# xmosio1.net
KiCad netlist of a schematic drawn in EAGLE
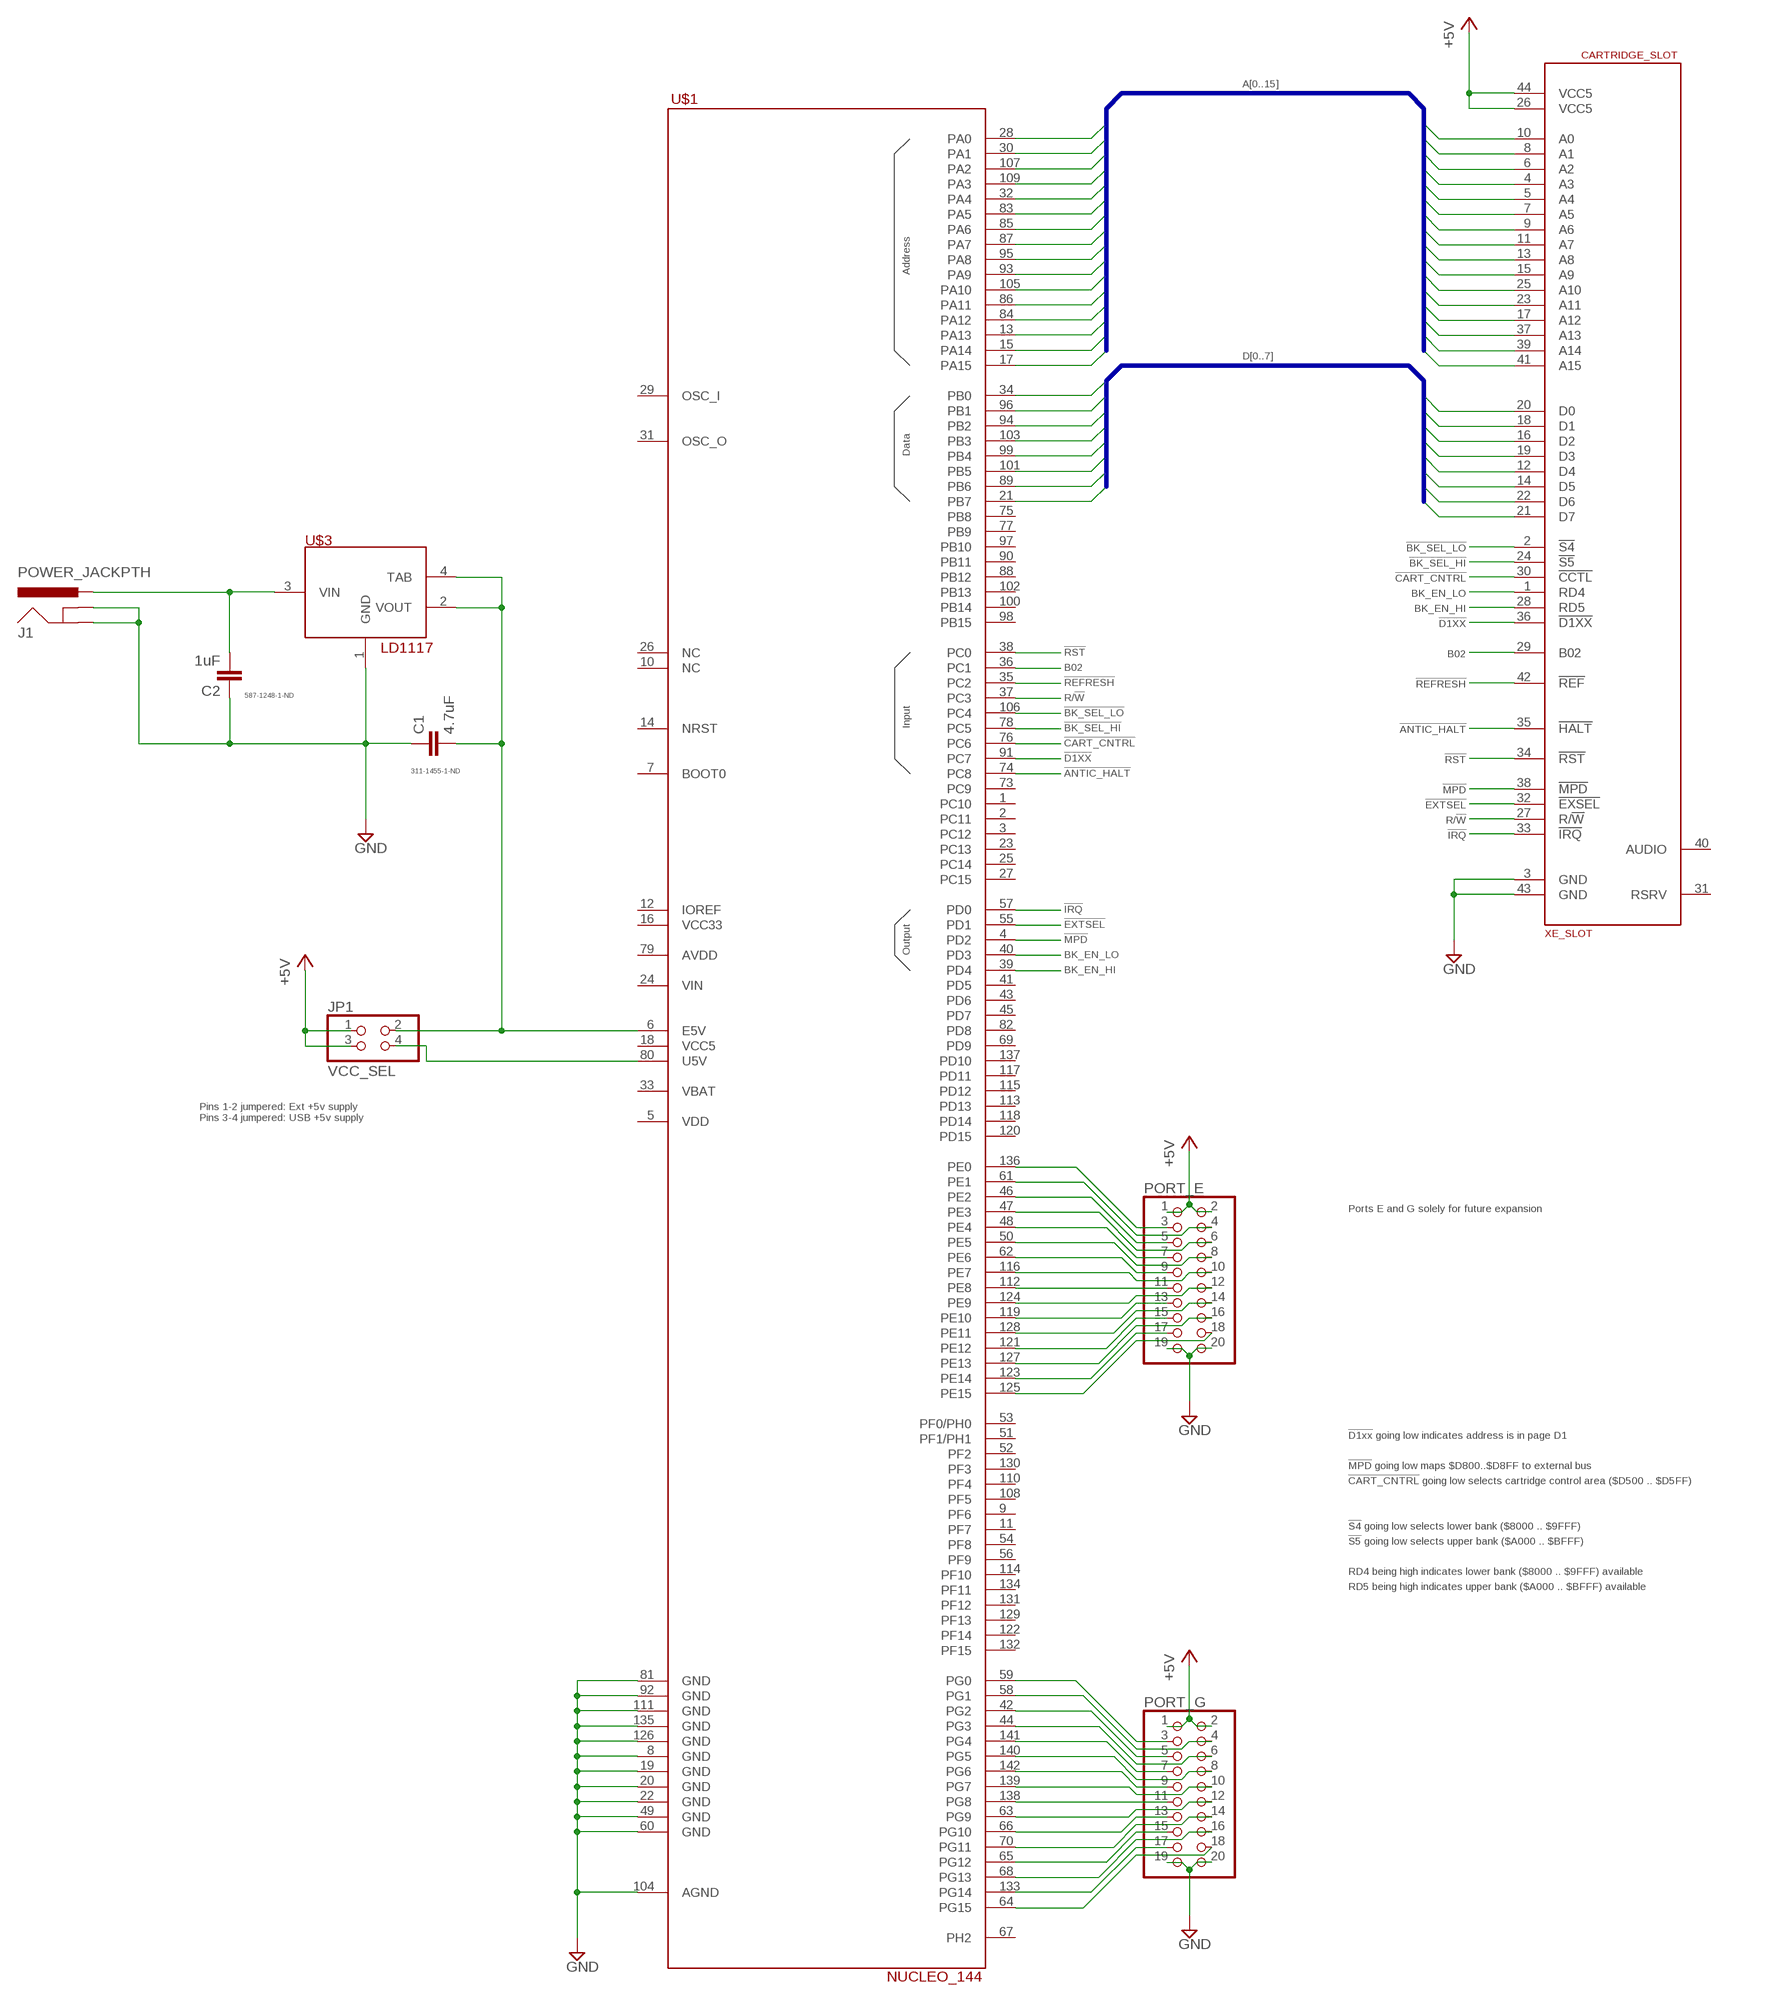
[diagram p0: schematic, sheet 1]

(export (version "E")
  (design (tool "Eeschema 10.0.6"))
  (components
    (comp (ref "C1")
      (value "4.7uF")
      (footprint "eagle-import:C0603")
      (libsource (lib "eagle-import") (part "C-EUC0603"))
    )
    (comp (ref "C2")
      (value "1uF")
      (footprint "eagle-import:C0603")
      (libsource (lib "eagle-import") (part "C-EUC0603"))
    )
    (comp (ref "CARTRIDGE_SLOT")
      (value "XE_SLOT")
      (footprint "eagle-import:XE_SLOT")
      (libsource (lib "eagle-import") (part "XE_SLOT"))
    )
    (comp (ref "J1")
      (value "POWER_JACKPTH")
      (footprint "eagle-import:POWER_JACK_PTH")
      (libsource (lib "eagle-import") (part "POWER_JACKPTH"))
    )
    (comp (ref "JP1")
      (value "VCC_SEL")
      (footprint "eagle-import:2X02")
      (libsource (lib "eagle-import") (part "PINHD-2X2"))
    )
    (comp (ref "PORT_E")
      (value "PINHD-2X10")
      (footprint "eagle-import:2X10")
      (libsource (lib "eagle-import") (part "PINHD-2X10"))
    )
    (comp (ref "PORT_G")
      (value "PINHD-2X10")
      (footprint "eagle-import:2X10")
      (libsource (lib "eagle-import") (part "PINHD-2X10"))
    )
    (comp (ref "U$1")
      (value "NUCLEO_144")
      (footprint "eagle-import:NUCLEO_144")
      (libsource (lib "eagle-import") (part "NUCLEO_144"))
    )
    (comp (ref "U$3")
      (value "LD1117")
      (footprint "eagle-import:SOT223")
      (libsource (lib "eagle-import") (part "LD1117"))
    )
  )
  (nets
    (net (code "1") (name "+5V") (class "Default")
      (node (ref "CARTRIDGE_SLOT") (pin "26") (pinfunction "VCC5_26") (pintype "bidirectional"))
      (node (ref "CARTRIDGE_SLOT") (pin "44") (pinfunction "VCC5_44") (pintype "bidirectional"))
      (node (ref "JP1") (pin "1") (pinfunction "1_1") (pintype "passive"))
      (node (ref "JP1") (pin "3") (pinfunction "3_3") (pintype "passive"))
      (node (ref "PORT_E") (pin "1") (pinfunction "1_1") (pintype "passive"))
      (node (ref "PORT_E") (pin "2") (pinfunction "2_2") (pintype "passive"))
      (node (ref "PORT_G") (pin "1") (pinfunction "1_1") (pintype "passive"))
      (node (ref "PORT_G") (pin "2") (pinfunction "2_2") (pintype "passive"))
    )
    (net (code "2") (name "/A0") (class "Default")
      (node (ref "CARTRIDGE_SLOT") (pin "10") (pinfunction "A0_10") (pintype "bidirectional"))
      (node (ref "U$1") (pin "28") (pinfunction "PA0_28") (pintype "bidirectional"))
    )
    (net (code "3") (name "/A1") (class "Default")
      (node (ref "CARTRIDGE_SLOT") (pin "8") (pinfunction "A1_8") (pintype "bidirectional"))
      (node (ref "U$1") (pin "30") (pinfunction "PA1_30") (pintype "bidirectional"))
    )
    (net (code "4") (name "/A2") (class "Default")
      (node (ref "CARTRIDGE_SLOT") (pin "6") (pinfunction "A2_6") (pintype "bidirectional"))
      (node (ref "U$1") (pin "107") (pinfunction "PA2_107") (pintype "bidirectional"))
    )
    (net (code "5") (name "/A3") (class "Default")
      (node (ref "CARTRIDGE_SLOT") (pin "4") (pinfunction "A3_4") (pintype "bidirectional"))
      (node (ref "U$1") (pin "109") (pinfunction "PA3_109") (pintype "bidirectional"))
    )
    (net (code "6") (name "/A4") (class "Default")
      (node (ref "CARTRIDGE_SLOT") (pin "5") (pinfunction "A4_5") (pintype "bidirectional"))
      (node (ref "U$1") (pin "32") (pinfunction "PA4_32") (pintype "bidirectional"))
    )
    (net (code "7") (name "/A5") (class "Default")
      (node (ref "CARTRIDGE_SLOT") (pin "7") (pinfunction "A5_7") (pintype "bidirectional"))
      (node (ref "U$1") (pin "83") (pinfunction "PA5_83") (pintype "bidirectional"))
    )
    (net (code "8") (name "/A6") (class "Default")
      (node (ref "CARTRIDGE_SLOT") (pin "9") (pinfunction "A6_9") (pintype "bidirectional"))
      (node (ref "U$1") (pin "85") (pinfunction "PA6_85") (pintype "bidirectional"))
    )
    (net (code "9") (name "/A7") (class "Default")
      (node (ref "CARTRIDGE_SLOT") (pin "11") (pinfunction "A7_11") (pintype "bidirectional"))
      (node (ref "U$1") (pin "87") (pinfunction "PA7_87") (pintype "bidirectional"))
    )
    (net (code "10") (name "/A8") (class "Default")
      (node (ref "CARTRIDGE_SLOT") (pin "13") (pinfunction "A8_13") (pintype "bidirectional"))
      (node (ref "U$1") (pin "95") (pinfunction "PA8_95") (pintype "bidirectional"))
    )
    (net (code "11") (name "/A9") (class "Default")
      (node (ref "CARTRIDGE_SLOT") (pin "15") (pinfunction "A9_15") (pintype "bidirectional"))
      (node (ref "U$1") (pin "93") (pinfunction "PA9_93") (pintype "bidirectional"))
    )
    (net (code "12") (name "/A10") (class "Default")
      (node (ref "CARTRIDGE_SLOT") (pin "25") (pinfunction "A10_25") (pintype "bidirectional"))
      (node (ref "U$1") (pin "105") (pinfunction "PA10_105") (pintype "bidirectional"))
    )
    (net (code "13") (name "/A11") (class "Default")
      (node (ref "CARTRIDGE_SLOT") (pin "23") (pinfunction "A11_23") (pintype "bidirectional"))
      (node (ref "U$1") (pin "86") (pinfunction "PA11_86") (pintype "bidirectional"))
    )
    (net (code "14") (name "/A12") (class "Default")
      (node (ref "CARTRIDGE_SLOT") (pin "17") (pinfunction "A12_17") (pintype "bidirectional"))
      (node (ref "U$1") (pin "84") (pinfunction "PA12_84") (pintype "bidirectional"))
    )
    (net (code "15") (name "/A13") (class "Default")
      (node (ref "CARTRIDGE_SLOT") (pin "37") (pinfunction "A13_37") (pintype "bidirectional"))
      (node (ref "U$1") (pin "13") (pinfunction "PA13_13") (pintype "bidirectional"))
    )
    (net (code "16") (name "/A14") (class "Default")
      (node (ref "CARTRIDGE_SLOT") (pin "39") (pinfunction "A14_39") (pintype "bidirectional"))
      (node (ref "U$1") (pin "15") (pinfunction "PA14_15") (pintype "bidirectional"))
    )
    (net (code "17") (name "/A15") (class "Default")
      (node (ref "CARTRIDGE_SLOT") (pin "41") (pinfunction "A15_41") (pintype "bidirectional"))
      (node (ref "U$1") (pin "17") (pinfunction "PA15_17") (pintype "bidirectional"))
    )
    (net (code "19") (name "/B02") (class "Default")
      (node (ref "CARTRIDGE_SLOT") (pin "29") (pinfunction "B02_29") (pintype "bidirectional"))
      (node (ref "U$1") (pin "36") (pinfunction "PC1_36") (pintype "bidirectional"))
    )
    (net (code "20") (name "/BK_EN_HI") (class "Default")
      (node (ref "CARTRIDGE_SLOT") (pin "28") (pinfunction "RD5_28") (pintype "bidirectional"))
      (node (ref "U$1") (pin "39") (pinfunction "PD4_39") (pintype "bidirectional"))
    )
    (net (code "21") (name "/BK_EN_LO") (class "Default")
      (node (ref "CARTRIDGE_SLOT") (pin "1") (pinfunction "RD4_1") (pintype "bidirectional"))
      (node (ref "U$1") (pin "40") (pinfunction "PD3_40") (pintype "bidirectional"))
    )
    (net (code "22") (name "/D0") (class "Default")
      (node (ref "CARTRIDGE_SLOT") (pin "20") (pinfunction "D0_20") (pintype "bidirectional"))
      (node (ref "U$1") (pin "34") (pinfunction "PB0_34") (pintype "bidirectional"))
    )
    (net (code "23") (name "/D1") (class "Default")
      (node (ref "CARTRIDGE_SLOT") (pin "18") (pinfunction "D1_18") (pintype "bidirectional"))
      (node (ref "U$1") (pin "96") (pinfunction "PB1_96") (pintype "bidirectional"))
    )
    (net (code "24") (name "/D2") (class "Default")
      (node (ref "CARTRIDGE_SLOT") (pin "16") (pinfunction "D2_16") (pintype "bidirectional"))
      (node (ref "U$1") (pin "94") (pinfunction "PB2_94") (pintype "bidirectional"))
    )
    (net (code "25") (name "/D3") (class "Default")
      (node (ref "CARTRIDGE_SLOT") (pin "19") (pinfunction "D3_19") (pintype "bidirectional"))
      (node (ref "U$1") (pin "103") (pinfunction "PB3_103") (pintype "bidirectional"))
    )
    (net (code "26") (name "/D4") (class "Default")
      (node (ref "CARTRIDGE_SLOT") (pin "12") (pinfunction "D4_12") (pintype "bidirectional"))
      (node (ref "U$1") (pin "99") (pinfunction "PB4_99") (pintype "bidirectional"))
    )
    (net (code "27") (name "/D5") (class "Default")
      (node (ref "CARTRIDGE_SLOT") (pin "14") (pinfunction "D5_14") (pintype "bidirectional"))
      (node (ref "U$1") (pin "101") (pinfunction "PB5_101") (pintype "bidirectional"))
    )
    (net (code "28") (name "/D6") (class "Default")
      (node (ref "CARTRIDGE_SLOT") (pin "22") (pinfunction "D6_22") (pintype "bidirectional"))
      (node (ref "U$1") (pin "89") (pinfunction "PB6_89") (pintype "bidirectional"))
    )
    (net (code "29") (name "/D7") (class "Default")
      (node (ref "CARTRIDGE_SLOT") (pin "21") (pinfunction "D7_21") (pintype "bidirectional"))
      (node (ref "U$1") (pin "21") (pinfunction "PB7_21") (pintype "bidirectional"))
    )
    (net (code "31") (name "/R{slash}~{W}") (class "Default")
      (node (ref "CARTRIDGE_SLOT") (pin "27") (pinfunction "R/~{W}_27") (pintype "bidirectional"))
      (node (ref "U$1") (pin "37") (pinfunction "PC3_37") (pintype "bidirectional"))
    )
    (net (code "32") (name "/~{ANTIC_HALT}") (class "Default")
      (node (ref "CARTRIDGE_SLOT") (pin "35") (pinfunction "~{HALT}_35") (pintype "bidirectional"))
      (node (ref "U$1") (pin "74") (pinfunction "PC8_74") (pintype "bidirectional"))
    )
    (net (code "33") (name "/~{BK_SEL_HI}") (class "Default")
      (node (ref "CARTRIDGE_SLOT") (pin "24") (pinfunction "~{S5}_24") (pintype "bidirectional"))
      (node (ref "U$1") (pin "78") (pinfunction "PC5_78") (pintype "bidirectional"))
    )
    (net (code "34") (name "/~{BK_SEL_LO}") (class "Default")
      (node (ref "CARTRIDGE_SLOT") (pin "2") (pinfunction "~{S4}_2") (pintype "bidirectional"))
      (node (ref "U$1") (pin "106") (pinfunction "PC4_106") (pintype "bidirectional"))
    )
    (net (code "35") (name "/~{CART_CNTRL}") (class "Default")
      (node (ref "CARTRIDGE_SLOT") (pin "30") (pinfunction "~{CCTL}_30") (pintype "bidirectional"))
      (node (ref "U$1") (pin "76") (pinfunction "PC6_76") (pintype "bidirectional"))
    )
    (net (code "36") (name "/~{D1XX}") (class "Default")
      (node (ref "CARTRIDGE_SLOT") (pin "36") (pinfunction "~{D1XX}_36") (pintype "bidirectional"))
      (node (ref "U$1") (pin "91") (pinfunction "PC7_91") (pintype "bidirectional"))
    )
    (net (code "37") (name "/~{EXTSEL}") (class "Default")
      (node (ref "CARTRIDGE_SLOT") (pin "32") (pinfunction "~{EXSEL}_32") (pintype "bidirectional"))
      (node (ref "U$1") (pin "55") (pinfunction "PD1_55") (pintype "bidirectional"))
    )
    (net (code "38") (name "/~{IRQ}") (class "Default")
      (node (ref "CARTRIDGE_SLOT") (pin "33") (pinfunction "~{IRQ}_33") (pintype "bidirectional"))
      (node (ref "U$1") (pin "57") (pinfunction "PD0_57") (pintype "bidirectional"))
    )
    (net (code "39") (name "/~{MPD}") (class "Default")
      (node (ref "CARTRIDGE_SLOT") (pin "38") (pinfunction "~{MPD}_38") (pintype "bidirectional"))
      (node (ref "U$1") (pin "4") (pinfunction "PD2_4") (pintype "bidirectional"))
    )
    (net (code "40") (name "/~{REFRESH}") (class "Default")
      (node (ref "CARTRIDGE_SLOT") (pin "42") (pinfunction "~{REF}_42") (pintype "bidirectional"))
      (node (ref "U$1") (pin "35") (pinfunction "PC2_35") (pintype "bidirectional"))
    )
    (net (code "41") (name "/~{RST}") (class "Default")
      (node (ref "CARTRIDGE_SLOT") (pin "34") (pinfunction "~{RST}_34") (pintype "bidirectional"))
      (node (ref "U$1") (pin "38") (pinfunction "PC0_38") (pintype "bidirectional"))
    )
    (net (code "42") (name "GND") (class "Default")
      (node (ref "C1") (pin "1") (pinfunction "1_1") (pintype "passive"))
      (node (ref "C2") (pin "1") (pinfunction "1_1") (pintype "passive"))
      (node (ref "CARTRIDGE_SLOT") (pin "3") (pinfunction "GND_3") (pintype "bidirectional"))
      (node (ref "CARTRIDGE_SLOT") (pin "43") (pinfunction "GND_43") (pintype "bidirectional"))
      (node (ref "J1") (pin "GND") (pinfunction "GND_GND") (pintype "bidirectional"))
      (node (ref "J1") (pin "GNDBREAK") (pinfunction "GNDBREAK_GNDBREAK") (pintype "bidirectional"))
      (node (ref "PORT_E") (pin "19") (pinfunction "19_19") (pintype "passive"))
      (node (ref "PORT_E") (pin "20") (pinfunction "20_20") (pintype "passive"))
      (node (ref "PORT_G") (pin "19") (pinfunction "19_19") (pintype "passive"))
      (node (ref "PORT_G") (pin "20") (pinfunction "20_20") (pintype "passive"))
      (node (ref "U$1") (pin "104") (pinfunction "AGND_104") (pintype "bidirectional"))
      (node (ref "U$1") (pin "111") (pinfunction "GND_111") (pintype "bidirectional"))
      (node (ref "U$1") (pin "126") (pinfunction "GND_126") (pintype "bidirectional"))
      (node (ref "U$1") (pin "135") (pinfunction "GND_135") (pintype "bidirectional"))
      (node (ref "U$1") (pin "19") (pinfunction "GND_19") (pintype "bidirectional"))
      (node (ref "U$1") (pin "20") (pinfunction "GND_20") (pintype "bidirectional"))
      (node (ref "U$1") (pin "22") (pinfunction "GND_22") (pintype "bidirectional"))
      (node (ref "U$1") (pin "49") (pinfunction "GND_49") (pintype "bidirectional"))
      (node (ref "U$1") (pin "60") (pinfunction "GND_60") (pintype "bidirectional"))
      (node (ref "U$1") (pin "8") (pinfunction "GND_8") (pintype "bidirectional"))
      (node (ref "U$1") (pin "81") (pinfunction "GND_81") (pintype "bidirectional"))
      (node (ref "U$1") (pin "92") (pinfunction "GND_92") (pintype "bidirectional"))
      (node (ref "U$3") (pin "1") (pinfunction "GND_1") (pintype "bidirectional"))
    )
    (net (code "43") (name "Net-(U$1-E5V)") (class "Default")
      (node (ref "C1") (pin "2") (pinfunction "2_2") (pintype "passive"))
      (node (ref "JP1") (pin "2") (pinfunction "2_2") (pintype "passive"))
      (node (ref "U$1") (pin "6") (pinfunction "E5V_6") (pintype "bidirectional"))
      (node (ref "U$3") (pin "2") (pinfunction "VOUT_2") (pintype "bidirectional"))
      (node (ref "U$3") (pin "4") (pinfunction "TAB_4") (pintype "bidirectional"))
    )
    (net (code "44") (name "Net-(U$1-PE0)") (class "Default")
      (node (ref "PORT_E") (pin "3") (pinfunction "3_3") (pintype "passive"))
      (node (ref "U$1") (pin "136") (pinfunction "PE0_136") (pintype "bidirectional"))
    )
    (net (code "45") (name "Net-(U$1-PE1)") (class "Default")
      (node (ref "PORT_E") (pin "4") (pinfunction "4_4") (pintype "passive"))
      (node (ref "U$1") (pin "61") (pinfunction "PE1_61") (pintype "bidirectional"))
    )
    (net (code "46") (name "Net-(U$1-PE2)") (class "Default")
      (node (ref "PORT_E") (pin "5") (pinfunction "5_5") (pintype "passive"))
      (node (ref "U$1") (pin "46") (pinfunction "PE2_46") (pintype "bidirectional"))
    )
    (net (code "47") (name "Net-(U$1-PE3)") (class "Default")
      (node (ref "PORT_E") (pin "6") (pinfunction "6_6") (pintype "passive"))
      (node (ref "U$1") (pin "47") (pinfunction "PE3_47") (pintype "bidirectional"))
    )
    (net (code "48") (name "Net-(U$1-PE4)") (class "Default")
      (node (ref "PORT_E") (pin "7") (pinfunction "7_7") (pintype "passive"))
      (node (ref "U$1") (pin "48") (pinfunction "PE4_48") (pintype "bidirectional"))
    )
    (net (code "49") (name "Net-(U$1-PE5)") (class "Default")
      (node (ref "PORT_E") (pin "8") (pinfunction "8_8") (pintype "passive"))
      (node (ref "U$1") (pin "50") (pinfunction "PE5_50") (pintype "bidirectional"))
    )
    (net (code "50") (name "Net-(U$1-PE6)") (class "Default")
      (node (ref "PORT_E") (pin "9") (pinfunction "9_9") (pintype "passive"))
      (node (ref "U$1") (pin "62") (pinfunction "PE6_62") (pintype "bidirectional"))
    )
    (net (code "51") (name "Net-(U$1-PE7)") (class "Default")
      (node (ref "PORT_E") (pin "10") (pinfunction "10_10") (pintype "passive"))
      (node (ref "U$1") (pin "116") (pinfunction "PE7_116") (pintype "bidirectional"))
    )
    (net (code "52") (name "Net-(U$1-PE8)") (class "Default")
      (node (ref "PORT_E") (pin "11") (pinfunction "11_11") (pintype "passive"))
      (node (ref "U$1") (pin "112") (pinfunction "PE8_112") (pintype "bidirectional"))
    )
    (net (code "53") (name "Net-(U$1-PE9)") (class "Default")
      (node (ref "PORT_E") (pin "12") (pinfunction "12_12") (pintype "passive"))
      (node (ref "U$1") (pin "124") (pinfunction "PE9_124") (pintype "bidirectional"))
    )
    (net (code "54") (name "Net-(U$1-PE10)") (class "Default")
      (node (ref "PORT_E") (pin "13") (pinfunction "13_13") (pintype "passive"))
      (node (ref "U$1") (pin "119") (pinfunction "PE10_119") (pintype "bidirectional"))
    )
    (net (code "55") (name "Net-(U$1-PE11)") (class "Default")
      (node (ref "PORT_E") (pin "14") (pinfunction "14_14") (pintype "passive"))
      (node (ref "U$1") (pin "128") (pinfunction "PE11_128") (pintype "bidirectional"))
    )
    (net (code "56") (name "Net-(U$1-PE12)") (class "Default")
      (node (ref "PORT_E") (pin "15") (pinfunction "15_15") (pintype "passive"))
      (node (ref "U$1") (pin "121") (pinfunction "PE12_121") (pintype "bidirectional"))
    )
    (net (code "57") (name "Net-(U$1-PE13)") (class "Default")
      (node (ref "PORT_E") (pin "16") (pinfunction "16_16") (pintype "passive"))
      (node (ref "U$1") (pin "127") (pinfunction "PE13_127") (pintype "bidirectional"))
    )
    (net (code "58") (name "Net-(U$1-PE14)") (class "Default")
      (node (ref "PORT_E") (pin "17") (pinfunction "17_17") (pintype "passive"))
      (node (ref "U$1") (pin "123") (pinfunction "PE14_123") (pintype "bidirectional"))
    )
    (net (code "59") (name "Net-(U$1-PE15)") (class "Default")
      (node (ref "PORT_E") (pin "18") (pinfunction "18_18") (pintype "passive"))
      (node (ref "U$1") (pin "125") (pinfunction "PE15_125") (pintype "bidirectional"))
    )
    (net (code "60") (name "Net-(U$1-PG0)") (class "Default")
      (node (ref "PORT_G") (pin "3") (pinfunction "3_3") (pintype "passive"))
      (node (ref "U$1") (pin "59") (pinfunction "PG0_59") (pintype "bidirectional"))
    )
    (net (code "61") (name "Net-(U$1-PG1)") (class "Default")
      (node (ref "PORT_G") (pin "4") (pinfunction "4_4") (pintype "passive"))
      (node (ref "U$1") (pin "58") (pinfunction "PG1_58") (pintype "bidirectional"))
    )
    (net (code "62") (name "Net-(U$1-PG2)") (class "Default")
      (node (ref "PORT_G") (pin "5") (pinfunction "5_5") (pintype "passive"))
      (node (ref "U$1") (pin "42") (pinfunction "PG2_42") (pintype "bidirectional"))
    )
    (net (code "63") (name "Net-(U$1-PG3)") (class "Default")
      (node (ref "PORT_G") (pin "6") (pinfunction "6_6") (pintype "passive"))
      (node (ref "U$1") (pin "44") (pinfunction "PG3_44") (pintype "bidirectional"))
    )
    (net (code "64") (name "Net-(U$1-PG4)") (class "Default")
      (node (ref "PORT_G") (pin "7") (pinfunction "7_7") (pintype "passive"))
      (node (ref "U$1") (pin "141") (pinfunction "PG4_141") (pintype "bidirectional"))
    )
    (net (code "65") (name "Net-(U$1-PG5)") (class "Default")
      (node (ref "PORT_G") (pin "8") (pinfunction "8_8") (pintype "passive"))
      (node (ref "U$1") (pin "140") (pinfunction "PG5_140") (pintype "bidirectional"))
    )
    (net (code "66") (name "Net-(U$1-PG6)") (class "Default")
      (node (ref "PORT_G") (pin "9") (pinfunction "9_9") (pintype "passive"))
      (node (ref "U$1") (pin "142") (pinfunction "PG6_142") (pintype "bidirectional"))
    )
    (net (code "67") (name "Net-(U$1-PG7)") (class "Default")
      (node (ref "PORT_G") (pin "10") (pinfunction "10_10") (pintype "passive"))
      (node (ref "U$1") (pin "139") (pinfunction "PG7_139") (pintype "bidirectional"))
    )
    (net (code "68") (name "Net-(U$1-PG8)") (class "Default")
      (node (ref "PORT_G") (pin "11") (pinfunction "11_11") (pintype "passive"))
      (node (ref "U$1") (pin "138") (pinfunction "PG8_138") (pintype "bidirectional"))
    )
    (net (code "69") (name "Net-(U$1-PG9)") (class "Default")
      (node (ref "PORT_G") (pin "12") (pinfunction "12_12") (pintype "passive"))
      (node (ref "U$1") (pin "63") (pinfunction "PG9_63") (pintype "bidirectional"))
    )
    (net (code "70") (name "Net-(U$1-PG10)") (class "Default")
      (node (ref "PORT_G") (pin "13") (pinfunction "13_13") (pintype "passive"))
      (node (ref "U$1") (pin "66") (pinfunction "PG10_66") (pintype "bidirectional"))
    )
    (net (code "71") (name "Net-(U$1-PG11)") (class "Default")
      (node (ref "PORT_G") (pin "14") (pinfunction "14_14") (pintype "passive"))
      (node (ref "U$1") (pin "70") (pinfunction "PG11_70") (pintype "bidirectional"))
    )
    (net (code "72") (name "Net-(U$1-PG12)") (class "Default")
      (node (ref "PORT_G") (pin "15") (pinfunction "15_15") (pintype "passive"))
      (node (ref "U$1") (pin "65") (pinfunction "PG12_65") (pintype "bidirectional"))
    )
    (net (code "73") (name "Net-(U$1-PG13)") (class "Default")
      (node (ref "PORT_G") (pin "16") (pinfunction "16_16") (pintype "passive"))
      (node (ref "U$1") (pin "68") (pinfunction "PG13_68") (pintype "bidirectional"))
    )
    (net (code "74") (name "Net-(U$1-PG14)") (class "Default")
      (node (ref "PORT_G") (pin "17") (pinfunction "17_17") (pintype "passive"))
      (node (ref "U$1") (pin "133") (pinfunction "PG14_133") (pintype "bidirectional"))
    )
    (net (code "75") (name "Net-(U$1-PG15)") (class "Default")
      (node (ref "PORT_G") (pin "18") (pinfunction "18_18") (pintype "passive"))
      (node (ref "U$1") (pin "64") (pinfunction "PG15_64") (pintype "bidirectional"))
    )
    (net (code "76") (name "Net-(U$1-U5V)") (class "Default")
      (node (ref "JP1") (pin "4") (pinfunction "4_4") (pintype "passive"))
      (node (ref "U$1") (pin "80") (pinfunction "U5V_80") (pintype "bidirectional"))
    )
    (net (code "77") (name "Net-(U$3-VIN)") (class "Default")
      (node (ref "C2") (pin "2") (pinfunction "2_2") (pintype "passive"))
      (node (ref "J1") (pin "PWR") (pinfunction "PWR_PWR") (pintype "bidirectional"))
      (node (ref "U$3") (pin "3") (pinfunction "VIN_3") (pintype "bidirectional"))
    )
    (net (code "78") (name "unconnected-(CARTRIDGE_SLOT-AUDIO-Pad40)") (class "Default")
      (node (ref "CARTRIDGE_SLOT") (pin "40") (pinfunction "AUDIO_40") (pintype "bidirectional"))
    )
    (net (code "79") (name "unconnected-(CARTRIDGE_SLOT-RSRV-Pad31)") (class "Default")
      (node (ref "CARTRIDGE_SLOT") (pin "31") (pinfunction "RSRV_31") (pintype "bidirectional"))
    )
    (net (code "80") (name "unconnected-(U$1-AVDD-Pad79)") (class "Default")
      (node (ref "U$1") (pin "79") (pinfunction "AVDD_79") (pintype "bidirectional"))
    )
    (net (code "81") (name "unconnected-(U$1-BOOT0-Pad7)") (class "Default")
      (node (ref "U$1") (pin "7") (pinfunction "BOOT0_7") (pintype "bidirectional"))
    )
    (net (code "82") (name "unconnected-(U$1-IOREF-Pad12)") (class "Default")
      (node (ref "U$1") (pin "12") (pinfunction "IOREF_12") (pintype "bidirectional"))
    )
    (net (code "83") (name "unconnected-(U$1-NC-Pad10)") (class "Default")
      (node (ref "U$1") (pin "10") (pinfunction "NC_10") (pintype "bidirectional"))
    )
    (net (code "84") (name "unconnected-(U$1-NC-Pad26)") (class "Default")
      (node (ref "U$1") (pin "26") (pinfunction "NC_26") (pintype "bidirectional"))
    )
    (net (code "85") (name "unconnected-(U$1-NRST-Pad14)") (class "Default")
      (node (ref "U$1") (pin "14") (pinfunction "NRST_14") (pintype "bidirectional"))
    )
    (net (code "86") (name "unconnected-(U$1-OSC_I-Pad29)") (class "Default")
      (node (ref "U$1") (pin "29") (pinfunction "OSC_I_29") (pintype "bidirectional"))
    )
    (net (code "87") (name "unconnected-(U$1-OSC_O-Pad31)") (class "Default")
      (node (ref "U$1") (pin "31") (pinfunction "OSC_O_31") (pintype "bidirectional"))
    )
    (net (code "88") (name "unconnected-(U$1-PB8-Pad75)") (class "Default")
      (node (ref "U$1") (pin "75") (pinfunction "PB8_75") (pintype "bidirectional"))
    )
    (net (code "89") (name "unconnected-(U$1-PB9-Pad77)") (class "Default")
      (node (ref "U$1") (pin "77") (pinfunction "PB9_77") (pintype "bidirectional"))
    )
    (net (code "90") (name "unconnected-(U$1-PB10-Pad97)") (class "Default")
      (node (ref "U$1") (pin "97") (pinfunction "PB10_97") (pintype "bidirectional"))
    )
    (net (code "91") (name "unconnected-(U$1-PB11-Pad90)") (class "Default")
      (node (ref "U$1") (pin "90") (pinfunction "PB11_90") (pintype "bidirectional"))
    )
    (net (code "92") (name "unconnected-(U$1-PB12-Pad88)") (class "Default")
      (node (ref "U$1") (pin "88") (pinfunction "PB12_88") (pintype "bidirectional"))
    )
    (net (code "93") (name "unconnected-(U$1-PB13-Pad102)") (class "Default")
      (node (ref "U$1") (pin "102") (pinfunction "PB13_102") (pintype "bidirectional"))
    )
    (net (code "94") (name "unconnected-(U$1-PB14-Pad100)") (class "Default")
      (node (ref "U$1") (pin "100") (pinfunction "PB14_100") (pintype "bidirectional"))
    )
    (net (code "95") (name "unconnected-(U$1-PB15-Pad98)") (class "Default")
      (node (ref "U$1") (pin "98") (pinfunction "PB15_98") (pintype "bidirectional"))
    )
    (net (code "96") (name "unconnected-(U$1-PC9-Pad73)") (class "Default")
      (node (ref "U$1") (pin "73") (pinfunction "PC9_73") (pintype "bidirectional"))
    )
    (net (code "97") (name "unconnected-(U$1-PC10-Pad1)") (class "Default")
      (node (ref "U$1") (pin "1") (pinfunction "PC10_1") (pintype "bidirectional"))
    )
    (net (code "98") (name "unconnected-(U$1-PC11-Pad2)") (class "Default")
      (node (ref "U$1") (pin "2") (pinfunction "PC11_2") (pintype "bidirectional"))
    )
    (net (code "99") (name "unconnected-(U$1-PC12-Pad3)") (class "Default")
      (node (ref "U$1") (pin "3") (pinfunction "PC12_3") (pintype "bidirectional"))
    )
    (net (code "100") (name "unconnected-(U$1-PC13-Pad23)") (class "Default")
      (node (ref "U$1") (pin "23") (pinfunction "PC13_23") (pintype "bidirectional"))
    )
    (net (code "101") (name "unconnected-(U$1-PC14-Pad25)") (class "Default")
      (node (ref "U$1") (pin "25") (pinfunction "PC14_25") (pintype "bidirectional"))
    )
    (net (code "102") (name "unconnected-(U$1-PC15-Pad27)") (class "Default")
      (node (ref "U$1") (pin "27") (pinfunction "PC15_27") (pintype "bidirectional"))
    )
    (net (code "103") (name "unconnected-(U$1-PD5-Pad41)") (class "Default")
      (node (ref "U$1") (pin "41") (pinfunction "PD5_41") (pintype "bidirectional"))
    )
    (net (code "104") (name "unconnected-(U$1-PD6-Pad43)") (class "Default")
      (node (ref "U$1") (pin "43") (pinfunction "PD6_43") (pintype "bidirectional"))
    )
    (net (code "105") (name "unconnected-(U$1-PD7-Pad45)") (class "Default")
      (node (ref "U$1") (pin "45") (pinfunction "PD7_45") (pintype "bidirectional"))
    )
    (net (code "106") (name "unconnected-(U$1-PD8-Pad82)") (class "Default")
      (node (ref "U$1") (pin "82") (pinfunction "PD8_82") (pintype "bidirectional"))
    )
    (net (code "107") (name "unconnected-(U$1-PD9-Pad69)") (class "Default")
      (node (ref "U$1") (pin "69") (pinfunction "PD9_69") (pintype "bidirectional"))
    )
    (net (code "108") (name "unconnected-(U$1-PD10-Pad137)") (class "Default")
      (node (ref "U$1") (pin "137") (pinfunction "PD10_137") (pintype "bidirectional"))
    )
    (net (code "109") (name "unconnected-(U$1-PD11-Pad117)") (class "Default")
      (node (ref "U$1") (pin "117") (pinfunction "PD11_117") (pintype "bidirectional"))
    )
    (net (code "110") (name "unconnected-(U$1-PD12-Pad115)") (class "Default")
      (node (ref "U$1") (pin "115") (pinfunction "PD12_115") (pintype "bidirectional"))
    )
    (net (code "111") (name "unconnected-(U$1-PD13-Pad113)") (class "Default")
      (node (ref "U$1") (pin "113") (pinfunction "PD13_113") (pintype "bidirectional"))
    )
    (net (code "112") (name "unconnected-(U$1-PD14-Pad118)") (class "Default")
      (node (ref "U$1") (pin "118") (pinfunction "PD14_118") (pintype "bidirectional"))
    )
    (net (code "113") (name "unconnected-(U$1-PD15-Pad120)") (class "Default")
      (node (ref "U$1") (pin "120") (pinfunction "PD15_120") (pintype "bidirectional"))
    )
    (net (code "114") (name "unconnected-(U$1-PF0{slash}PH0-Pad53)") (class "Default")
      (node (ref "U$1") (pin "53") (pinfunction "PF0/PH0_53") (pintype "bidirectional"))
    )
    (net (code "115") (name "unconnected-(U$1-PF1{slash}PH1-Pad51)") (class "Default")
      (node (ref "U$1") (pin "51") (pinfunction "PF1/PH1_51") (pintype "bidirectional"))
    )
    (net (code "116") (name "unconnected-(U$1-PF2-Pad52)") (class "Default")
      (node (ref "U$1") (pin "52") (pinfunction "PF2_52") (pintype "bidirectional"))
    )
    (net (code "117") (name "unconnected-(U$1-PF3-Pad130)") (class "Default")
      (node (ref "U$1") (pin "130") (pinfunction "PF3_130") (pintype "bidirectional"))
    )
    (net (code "118") (name "unconnected-(U$1-PF4-Pad110)") (class "Default")
      (node (ref "U$1") (pin "110") (pinfunction "PF4_110") (pintype "bidirectional"))
    )
    (net (code "119") (name "unconnected-(U$1-PF5-Pad108)") (class "Default")
      (node (ref "U$1") (pin "108") (pinfunction "PF5_108") (pintype "bidirectional"))
    )
    (net (code "120") (name "unconnected-(U$1-PF6-Pad9)") (class "Default")
      (node (ref "U$1") (pin "9") (pinfunction "PF6_9") (pintype "bidirectional"))
    )
    (net (code "121") (name "unconnected-(U$1-PF7-Pad11)") (class "Default")
      (node (ref "U$1") (pin "11") (pinfunction "PF7_11") (pintype "bidirectional"))
    )
    (net (code "122") (name "unconnected-(U$1-PF8-Pad54)") (class "Default")
      (node (ref "U$1") (pin "54") (pinfunction "PF8_54") (pintype "bidirectional"))
    )
    (net (code "123") (name "unconnected-(U$1-PF9-Pad56)") (class "Default")
      (node (ref "U$1") (pin "56") (pinfunction "PF9_56") (pintype "bidirectional"))
    )
    (net (code "124") (name "unconnected-(U$1-PF10-Pad114)") (class "Default")
      (node (ref "U$1") (pin "114") (pinfunction "PF10_114") (pintype "bidirectional"))
    )
    (net (code "125") (name "unconnected-(U$1-PF11-Pad134)") (class "Default")
      (node (ref "U$1") (pin "134") (pinfunction "PF11_134") (pintype "bidirectional"))
    )
    (net (code "126") (name "unconnected-(U$1-PF12-Pad131)") (class "Default")
      (node (ref "U$1") (pin "131") (pinfunction "PF12_131") (pintype "bidirectional"))
    )
    (net (code "127") (name "unconnected-(U$1-PF13-Pad129)") (class "Default")
      (node (ref "U$1") (pin "129") (pinfunction "PF13_129") (pintype "bidirectional"))
    )
    (net (code "128") (name "unconnected-(U$1-PF14-Pad122)") (class "Default")
      (node (ref "U$1") (pin "122") (pinfunction "PF14_122") (pintype "bidirectional"))
    )
    (net (code "129") (name "unconnected-(U$1-PF15-Pad132)") (class "Default")
      (node (ref "U$1") (pin "132") (pinfunction "PF15_132") (pintype "bidirectional"))
    )
    (net (code "130") (name "unconnected-(U$1-PH2-Pad67)") (class "Default")
      (node (ref "U$1") (pin "67") (pinfunction "PH2_67") (pintype "bidirectional"))
    )
    (net (code "131") (name "unconnected-(U$1-VBAT-Pad33)") (class "Default")
      (node (ref "U$1") (pin "33") (pinfunction "VBAT_33") (pintype "bidirectional"))
    )
    (net (code "132") (name "unconnected-(U$1-VCC5-Pad18)") (class "Default")
      (node (ref "U$1") (pin "18") (pinfunction "VCC5_18") (pintype "bidirectional"))
    )
    (net (code "133") (name "unconnected-(U$1-VCC33-Pad16)") (class "Default")
      (node (ref "U$1") (pin "16") (pinfunction "VCC33_16") (pintype "bidirectional"))
    )
    (net (code "134") (name "unconnected-(U$1-VDD-Pad5)") (class "Default")
      (node (ref "U$1") (pin "5") (pinfunction "VDD_5") (pintype "bidirectional"))
    )
    (net (code "135") (name "unconnected-(U$1-VIN-Pad24)") (class "Default")
      (node (ref "U$1") (pin "24") (pinfunction "VIN_24") (pintype "bidirectional"))
    )
  )
)
